# SCHEMA.net
KiCad netlist of a schematic drawn in Altium Designer
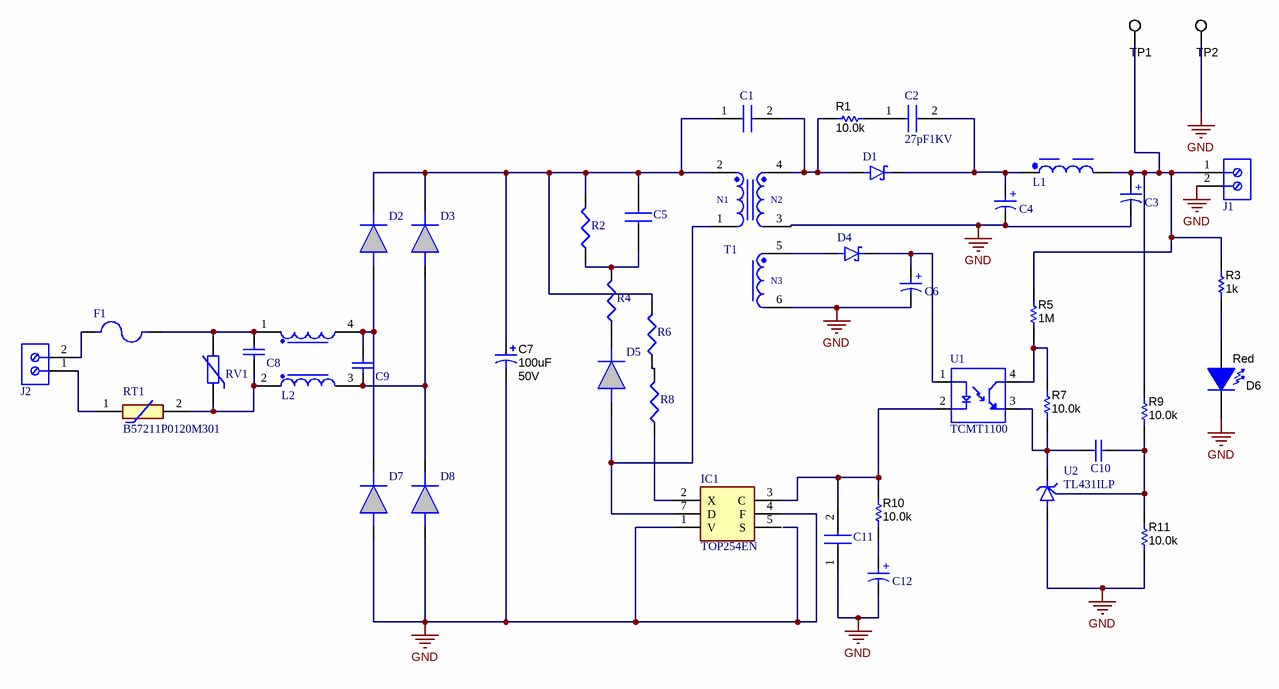
[diagram p0: SCHEMA.SchDoc]

(export (version "E")
  (design (tool "Eeschema 10.0.6"))
  (components
    (comp (ref "C1")
      (value "c270.22nf-250VAC")
      (footprint "440LT22R")
      (description "Capacitor")
      (fields
        (field (name "MANUFACTURER_PART_NUMBER") "440LT22-R")
        (field (name "MOUSER PART NUMBER") "75-440LT22-R")
      )
      (libsource (lib "INPUT_LIBRARY") (part "c270.22nf-250VAC"))
    )
    (comp (ref "C2")
      (value "27pF1KV")
      (footprint "S270K25SL0N63L6R")
      (description "Capacitor")
      (fields
        (field (name "MANUFACTURER_PART_NUMBER") "S270K25SL0N63L6R")
        (field (name "MOUSER PART NUMBER") "594-S270K25SL0N63L6R")
      )
      (libsource (lib "INPUT_LIBRARY") (part "27pF1KV"))
    )
    (comp (ref "C3")
      (value "180µF")
      (footprint "WCAP-PTG5_D8H8")
      (description "WCAP-PTG5 Aluminum Polymer Capacitor, Radial THT, D8 x H8mm, 180µF, 6.3V")
      (fields
        (field (name "MANUFACTURER PART NUMBER") "870025174001")
        (field (name "MANUFACTURER") "Wurth Elektronik")
      )
      (libsource (lib "INPUT_LIBRARY") (part "100uf 16v"))
    )
    (comp (ref "C4")
      (value "22uF")
      (footprint "WCAP-ATG8_D5H11")
      (description "WCAP-ATG8 Aluminum Electrolytic Capacitor, Radial, THT, D5 x H11mm, 22uF, 10V")
      (fields
        (field (name "MANUFACTURER PART NUMBER") "860010272001")
        (field (name "MANUFACTURER") "Wurth Elektronik")
      )
      (libsource (lib "INPUT_LIBRARY") (part "1800uf 25v"))
    )
    (comp (ref "C5")
      (value "FG26C0G2J391JNT06")
      (footprint "capacitor_ceramic")
      (description "MLCC with Dipped Radial Lead, Capacitance=390pF, LxWxT:5.5x6x3.5mm, Lead pitch:5mm")
      (fields (field (name "MOUSER PART NUMBER") "810-FG26C0G2J391JNT6"))
      (libsource (lib "INPUT_LIBRARY") (part "1.5 nF, 630 V, High Voltage Ceramic"))
    )
    (comp (ref "C6")
      (value "22uF")
      (footprint "WCAP-ATG8_D5H11")
      (description "WCAP-ATG8 Aluminum Electrolytic Capacitor, Radial, THT, D5 x H11mm, 22uF, 10V")
      (fields
        (field (name "MANUFACTURER PART NUMBER") "860010272001")
        (field (name "MANUFACTURER") "Wurth Elektronik")
      )
      (libsource (lib "INPUT_LIBRARY") (part "1800uf 25v"))
    )
    (comp (ref "C7")
      (value "UBT1H101MPD1TD")
      (footprint "BT_1000x1250")
      (description "CAP, AL, 100 uF, 50 V, +/- 20%, TH")
      (fields
        (field (name "MANUFACTURER") "Nichicon")
        (field (name "VALUEDISPLAYED") "100uF")
        (field (name "VDC_V") "50V")
        (field (name "PUBLISHER") "Texas Instruments")
      )
      (libsource (lib "INPUT_LIBRARY") (part "CMP-0009918-2"))
    )
    (comp (ref "C8")
      (value "15nF")
      (footprint "WCAP-FTX2_L11W6H10")
      (description "WCAP-FTX2 Film Capacitor, THT, L11 x W6 x H10mm, 15nF, 275V")
      (fields
        (field (name "MANUFACTURER PART NUMBER") "890324022007")
        (field (name "MANUFACTURER") "Wurth Elektronik")
      )
      (libsource (lib "INPUT_LIBRARY") (part "100nF275V iNPUT choke"))
    )
    (comp (ref "C9")
      (value "15nF")
      (footprint "WCAP-FTX2_L11W6H10")
      (description "WCAP-FTX2 Film Capacitor, THT, L11 x W6 x H10mm, 15nF, 275V")
      (fields
        (field (name "MANUFACTURER PART NUMBER") "890324022007")
        (field (name "MANUFACTURER") "Wurth Elektronik")
      )
      (libsource (lib "INPUT_LIBRARY") (part "100nF275V iNPUT choke"))
    )
    (comp (ref "C10")
      (value "15nF")
      (footprint "WCAP-FTX2_L11W6H10")
      (description "WCAP-FTX2 Film Capacitor, THT, L11 x W6 x H10mm, 15nF, 275V")
      (fields
        (field (name "MANUFACTURER PART NUMBER") "890324022007")
        (field (name "MANUFACTURER") "Wurth Elektronik")
      )
      (libsource (lib "INPUT_LIBRARY") (part "100nF275V iNPUT choke"))
    )
    (comp (ref "C11")
      (value "0.1 μF, 50 V, Ceramic, X7R")
      (footprint "C322")
      (description "Capacitor")
      (fields
        (field (name "MANUFACTURER_PART_NUMBER") "C322C104K5R5TA")
        (field (name "MOUSER PART NUMBER") "80-C322C104K5R")
      )
      (libsource (lib "INPUT_LIBRARY") (part "0.1 μF, 50 V, Ceramic, X7R"))
    )
    (comp (ref "C12")
      (value "180µF")
      (footprint "WCAP-PTG5_D8H8")
      (description "WCAP-PTG5 Aluminum Polymer Capacitor, Radial THT, D8 x H8mm, 180µF, 6.3V")
      (fields
        (field (name "MANUFACTURER PART NUMBER") "870025174001")
        (field (name "MANUFACTURER") "Wurth Elektronik")
      )
      (libsource (lib "INPUT_LIBRARY") (part "100uf 16v"))
    )
    (comp (ref "D1")
      (value "diode shotcky")
      (footprint "DIOM7959X265N")
      (description "Diode Schottky 40 V 3A Surface Mount SMC (DO-214AB)")
      (fields (field (name "MF") "ON Semiconductor") (field (name "MP") "SS34"))
      (libsource (lib "INPUT_LIBRARY") (part "diode shotcky"))
    )
    (comp (ref "D2")
      (value "1N4006-E3_54")
      (footprint "DIOAD1405W86L465D235")
      (description "Vishay 1N4006-E3/54 Diode, 800V 1A, 2-Pin DO-204AL")
      (fields
        (field (name "MOUSER PART NUMBER") "625-1N4006-E3/54")
        (field (name "MANUFACTURER_PART_NUMBER") "1N4006-E3/54")
      )
      (libsource (lib "INPUT_LIBRARY") (part "1N4006-E3_54_1"))
    )
    (comp (ref "D3")
      (value "1N4006-E3_54")
      (footprint "DIOAD1405W86L465D235")
      (description "Vishay 1N4006-E3/54 Diode, 800V 1A, 2-Pin DO-204AL")
      (fields
        (field (name "MOUSER PART NUMBER") "625-1N4006-E3/54")
        (field (name "MANUFACTURER_PART_NUMBER") "1N4006-E3/54")
      )
      (libsource (lib "INPUT_LIBRARY") (part "1N4006-E3_54_1"))
    )
    (comp (ref "D4")
      (value "diode shotcky")
      (footprint "DIOM7959X265N")
      (description "Diode Schottky 40 V 3A Surface Mount SMC (DO-214AB)")
      (fields (field (name "MF") "ON Semiconductor") (field (name "MP") "SS34"))
      (libsource (lib "INPUT_LIBRARY") (part "diode shotcky"))
    )
    (comp (ref "D5")
      (value "RMPG06K-E3_54")
      (footprint "DIOAD1271W66L305D242")
      (description "Rectifiers 800 Volt 1.0A 250ns 40 Amp IFSM")
      (fields
        (field (name "MOUSER PART NUMBER") "625-RMPG06K-E3")
        (field (name "MANUFACTURER_PART_NUMBER") "RMPG06K-E3/54")
      )
      (libsource (lib "INPUT_LIBRARY") (part "RMPG06K-E3_54"))
    )
    (comp (ref "D6")
      (value "Red")
      (footprint "LED_LTST-C190_Red")
      (description "LED, Red, SMD")
      (fields
        (field (name "PARTNUMBER") "LTST-C190CKT")
        (field (name "MANUFACTURER") "Lite-On")
        (field (name "PUBLISHER") "Texas Instruments")
      )
      (libsource (lib "INPUT_LIBRARY") (part "LTST-C190CKT"))
    )
    (comp (ref "D7")
      (value "1N4006-E3_54")
      (footprint "DIOAD1405W86L465D235")
      (description "Vishay 1N4006-E3/54 Diode, 800V 1A, 2-Pin DO-204AL")
      (fields
        (field (name "MOUSER PART NUMBER") "625-1N4006-E3/54")
        (field (name "MANUFACTURER_PART_NUMBER") "1N4006-E3/54")
      )
      (libsource (lib "INPUT_LIBRARY") (part "1N4006-E3_54_1"))
    )
    (comp (ref "D8")
      (value "1N4006-E3_54")
      (footprint "DIOAD1405W86L465D235")
      (description "Vishay 1N4006-E3/54 Diode, 800V 1A, 2-Pin DO-204AL")
      (fields
        (field (name "MOUSER PART NUMBER") "625-1N4006-E3/54")
        (field (name "MANUFACTURER_PART_NUMBER") "1N4006-E3/54")
      )
      (libsource (lib "INPUT_LIBRARY") (part "1N4006-E3_54_1"))
    )
    (comp (ref "F1")
      (value "fuse tht")
      (footprint "FUSE_0154004.DR")
      (description "2-Pin Radial Fuse ¦ Rectangular ¦ Slow Blow ¦ UL ¦ Bulk Pack ¦ 250mA")
      (fields (field (name "MP") "0697H9200-02"))
      (libsource (lib "INPUT_LIBRARY") (part "fuse tht"))
    )
    (comp (ref "IC1")
      (value "TOP254EN")
      (footprint "TOP265EG")
      (description "Integrated Circuit")
      (fields (field (name "MOUSER PART NUMBER") "869-TOP254EN"))
      (libsource (lib "INPUT_LIBRARY") (part "TOP254EN"))
    )
    (comp (ref "J1")
      (value "691101710002")
      (footprint "691103110002")
      (description "WR-TBL Series 101 Horizontal Entry Modular, THT, pitch 5mm, 2p")
      (fields (field (name "MANUFACTURER") "Wurth Elektronik"))
      (libsource (lib "INPUT_LIBRARY") (part "691101710002"))
    )
    (comp (ref "J2")
      (value "691101710002")
      (footprint "Model Name")
      (description "WR-TBL Series 101 Horizontal Entry Modular, THT, pitch 5mm, 2p")
      (fields (field (name "MANUFACTURER") "Wurth Elektronik"))
      (libsource (lib "INPUT_LIBRARY") (part "691101710002"))
    )
    (comp (ref "L1")
      (value "3900µH, 0.18A")
      (footprint "INDUCTOR_TH")
      (description "WE-TI Radial Leaded Wire Wound Inductor, size 8075, 3900µH, 0.18A, 12Ω")
      (fields
        (field (name "MANUFACTURER PART NUMBER") "744730392")
        (field (name "MANUFACTURER") "Wurth Elektronik")
      )
      (libsource (lib "INPUT_LIBRARY") (part "744730392"))
    )
    (comp (ref "L2")
      (value "39mH")
      (footprint "WE-CMB_Type L_L27.5W18.5H33")
      (description "WE-CMB Common Mode Power Line Choke, THT, Type XS, 39mH, 0.3A, 3000mOhm")
      (fields
        (field (name "MANUFACTURER PART NUMBER") "744821039")
        (field (name "MANUFACTURER") "Wurth Elektronik")
      )
      (libsource (lib "INPUT_LIBRARY") (part "744821039"))
    )
    (comp (ref "R1")
      (value "ERA-3ARW103V")
      (footprint "RES_0603")
      (description "RES, 10.0 k, 0.05%, 0.1 W, AEC-Q200 Grade 0, 0603")
      (fields (field (name "MANUFACTURER") "Panasonic") (field (name "VALUEDISPLAYED") "10.0k"))
      (libsource (lib "INPUT_LIBRARY") (part "REStht"))
    )
    (comp (ref "R2")
      (value "0.15Ω")
      (footprint "RESAD1590W60L630D240")
      (description "WRIS-KSKE Thick Film Resistor, SMT, size 0402, 0.125W, 0.15Ω, +/-1%")
      (fields
        (field (name "MANUFACTURER PART NUMBER") "560050310002")
        (field (name "MANUFACTURER") "Wurth Elektronik")
      )
      (libsource (lib "INPUT_LIBRARY") (part "RES-THT"))
    )
    (comp (ref "R3")
      (value "1k")
      (footprint "0402L")
      (description "RES, 510, 5%, 0.063 W, 0402")
      (fields
        (field (name "PARTNUMBER") "CRCW0402510RJNED")
        (field (name "MANUFACTURER") "Vishay-Dale")
        (field (name "PUBLISHER") "Texas Instruments")
      )
      (libsource (lib "INPUT_LIBRARY") (part "CRCW0402510RJNED"))
    )
    (comp (ref "R4")
      (value "0.15Ω")
      (footprint "RESAD1590W60L630D240")
      (description "WRIS-KSKE Thick Film Resistor, SMT, size 0402, 0.125W, 0.15Ω, +/-1%")
      (fields
        (field (name "MANUFACTURER PART NUMBER") "560050310002")
        (field (name "MANUFACTURER") "Wurth Elektronik")
      )
      (libsource (lib "INPUT_LIBRARY") (part "RES-THT"))
    )
    (comp (ref "R5")
      (value "ERA-3ARW103V")
      (footprint "0603L")
      (description "RES, 10.0 k, 0.05%, 0.1 W, AEC-Q200 Grade 0, 0603")
      (fields (field (name "MANUFACTURER") "Panasonic") (field (name "VALUEDISPLAYED") "1M"))
      (libsource (lib "INPUT_LIBRARY") (part "RES-10K-0603"))
    )
    (comp (ref "R6")
      (value "0.15Ω")
      (footprint "RESAD1590W60L630D240")
      (description "WRIS-KSKE Thick Film Resistor, SMT, size 0402, 0.125W, 0.15Ω, +/-1%")
      (fields
        (field (name "MANUFACTURER PART NUMBER") "560050310002")
        (field (name "MANUFACTURER") "Wurth Elektronik")
      )
      (libsource (lib "INPUT_LIBRARY") (part "RES-THT"))
    )
    (comp (ref "R7")
      (value "ERA-3ARW103V")
      (footprint "RES_0603")
      (description "RES, 10.0 k, 0.05%, 0.1 W, AEC-Q200 Grade 0, 0603")
      (fields (field (name "MANUFACTURER") "Panasonic") (field (name "VALUEDISPLAYED") "10.0k"))
      (libsource (lib "INPUT_LIBRARY") (part "REStht"))
    )
    (comp (ref "R8")
      (value "0.15Ω")
      (footprint "RESAD1590W60L630D240")
      (description "WRIS-KSKE Thick Film Resistor, SMT, size 0402, 0.125W, 0.15Ω, +/-1%")
      (fields
        (field (name "MANUFACTURER PART NUMBER") "560050310002")
        (field (name "MANUFACTURER") "Wurth Elektronik")
      )
      (libsource (lib "INPUT_LIBRARY") (part "RES-THT"))
    )
    (comp (ref "R9")
      (value "ERA-3ARW103V")
      (footprint "RES_0603")
      (description "RES, 10.0 k, 0.05%, 0.1 W, AEC-Q200 Grade 0, 0603")
      (fields (field (name "MANUFACTURER") "Panasonic") (field (name "VALUEDISPLAYED") "10.0k"))
      (libsource (lib "INPUT_LIBRARY") (part "REStht"))
    )
    (comp (ref "R10")
      (value "ERA-3ARW103V")
      (footprint "RES_0603")
      (description "RES, 10.0 k, 0.05%, 0.1 W, AEC-Q200 Grade 0, 0603")
      (fields (field (name "MANUFACTURER") "Panasonic") (field (name "VALUEDISPLAYED") "10.0k"))
      (libsource (lib "INPUT_LIBRARY") (part "REStht"))
    )
    (comp (ref "R11")
      (value "ERA-3ARW103V")
      (footprint "RES_0603")
      (description "RES, 10.0 k, 0.05%, 0.1 W, AEC-Q200 Grade 0, 0603")
      (fields (field (name "MANUFACTURER") "Panasonic") (field (name "VALUEDISPLAYED") "10.0k"))
      (libsource (lib "INPUT_LIBRARY") (part "REStht"))
    )
    (comp (ref "RT1")
      (value "B57211P0120M301")
      (footprint "B57211P0***M3*1")
      (description "Thermistor")
      (fields (field (name "MOUSER PART NUMBER") "871-B57211P0120M301"))
      (libsource (lib "INPUT_LIBRARY") (part "B57211P0120M301"))
    )
    (comp (ref "RV1")
      (value "130VAC, 170VDC")
      (footprint "VARISTOR")
      (description "WE-VD Disk Varistor, THT, 130VAC, 170VDC, 410pF")
      (fields
        (field (name "MANUFACTURER PART NUMBER") "820411311")
        (field (name "MANUFACTURER") "Wurth Elektronik")
      )
      (libsource (lib "INPUT_LIBRARY") (part "820411311"))
    )
    (comp (ref "T1")
      (value "85-265Vin, 5Vout")
      (footprint "TRANSFORMER_E22")
      (description "WE-UNIT Off-Line Transformer, THT, E13/7/4_Vertical, 85-265Vin, 5Vout, 3W")
      (fields
        (field (name "MANUFACTURER PART NUMBER") "749118105")
        (field (name "MANUFACTURER") "Wurth Elektronik")
      )
      (libsource (lib "INPUT_LIBRARY") (part "749118105"))
    )
    (comp (ref "TP1")
      (value "5016")
      (footprint "Testpoint_Keystone_Compact")
      (description "Test Point, Compact, SMT")
      (fields (field (name "MANUFACTURER") "Keystone") (field (name "PUBLISHER") "Texas Instruments"))
      (libsource (lib "INPUT_LIBRARY") (part "5016"))
    )
    (comp (ref "TP2")
      (value "5016")
      (footprint "Testpoint_Keystone_Compact")
      (description "Test Point, Compact, SMT")
      (fields (field (name "MANUFACTURER") "Keystone") (field (name "PUBLISHER") "Texas Instruments"))
      (libsource (lib "INPUT_LIBRARY") (part "5016"))
    )
    (comp (ref "U1")
      (value "TCMT1100")
      (footprint "SOIC127P700X230-4N")
      (description "Optoisolator Transistor Output 3750Vrms 1 Channel 4-SOP")
      (fields
        (field (name "DIGI-KEY_PART_NUMBER") "TCMT1100CT-ND")
        (field (name "MF") "Vishay Semiconductor")
      )
      (libsource (lib "INPUT_LIBRARY") (part "TCMT1100"))
    )
    (comp (ref "U2")
      (value "TL431ILP")
      (footprint "TL431CLP")
      (description "Ic, Tl431ilp, Tl431, Tl431a, Tl4 31b, Tl432, Tl432a, Tl432b<Nv")
      (libsource (lib "INPUT_LIBRARY") (part "TL431ILP"))
    )
  )
  (nets
    (net (code "1") (name "GND") (class "Default")
      (node (ref "C11") (pin "1") (pinfunction "1_1") (pintype "passive"))
      (node (ref "C12") (pin "2") (pinfunction "N_2") (pintype "passive"))
      (node (ref "C3") (pin "2") (pinfunction "N_2") (pintype "passive"))
      (node (ref "C4") (pin "2") (pinfunction "N_2") (pintype "passive"))
      (node (ref "C6") (pin "2") (pinfunction "N_2") (pintype "passive"))
      (node (ref "C7") (pin "2") (pinfunction "-_2") (pintype "passive"))
      (node (ref "D6") (pin "2") (pinfunction "K_2") (pintype "passive"))
      (node (ref "D7") (pin "2") (pinfunction "A_2") (pintype "passive"))
      (node (ref "D8") (pin "2") (pinfunction "A_2") (pintype "passive"))
      (node (ref "IC1") (pin "1") (pinfunction "V_1") (pintype "passive"))
      (node (ref "IC1") (pin "4") (pinfunction "F_4") (pintype "passive"))
      (node (ref "J1") (pin "2") (pinfunction "2_2") (pintype "power_in"))
      (node (ref "R11") (pin "1") (pinfunction "1_1") (pintype "passive"))
      (node (ref "T1") (pin "3") (pinfunction "6_3") (pintype "passive"))
      (node (ref "T1") (pin "6") (pinfunction "6_6") (pintype "passive"))
      (node (ref "TP2") (pin "1") (pintype "passive"))
      (node (ref "U2") (pin "2") (pinfunction "A_2") (pintype "passive"))
    )
    (net (code "2") (name "Net-(C1-Pad2)") (class "Default")
      (node (ref "C1") (pin "2") (pinfunction "2_2") (pintype "passive"))
      (node (ref "D1") (pin "A") (pinfunction "A_A") (pintype "passive"))
      (node (ref "R1") (pin "2") (pinfunction "2_2") (pintype "passive"))
      (node (ref "T1") (pin "4") (pinfunction "4_4") (pintype "passive"))
    )
    (net (code "3") (name "Net-(C2-Pad1)") (class "Default")
      (node (ref "C2") (pin "1") (pinfunction "1_1") (pintype "passive"))
      (node (ref "R1") (pin "1") (pinfunction "1_1") (pintype "passive"))
    )
    (net (code "4") (name "Net-(C3-P)") (class "Default")
      (node (ref "C3") (pin "1") (pinfunction "P_1") (pintype "passive"))
      (node (ref "J1") (pin "1") (pinfunction "1_1") (pintype "power_in"))
      (node (ref "L1") (pin "2") (pinfunction "2_2") (pintype "passive"))
      (node (ref "R3") (pin "2") (pinfunction "2_2") (pintype "passive"))
      (node (ref "R5") (pin "1") (pinfunction "1_1") (pintype "passive"))
      (node (ref "R9") (pin "2") (pinfunction "2_2") (pintype "passive"))
      (node (ref "TP1") (pin "1") (pintype "passive"))
    )
    (net (code "5") (name "Net-(C4-P)") (class "Default")
      (node (ref "C2") (pin "2") (pinfunction "2_2") (pintype "passive"))
      (node (ref "C4") (pin "1") (pinfunction "P_1") (pintype "passive"))
      (node (ref "D1") (pin "C") (pinfunction "K_C") (pintype "passive"))
      (node (ref "L1") (pin "1") (pinfunction "1_1") (pintype "passive"))
    )
    (net (code "6") (name "Net-(C5-Pad2)") (class "Default")
      (node (ref "C5") (pin "2") (pinfunction "2_2") (pintype "passive"))
      (node (ref "R2") (pin "1") (pinfunction "1_1") (pintype "passive"))
      (node (ref "R4") (pin "2") (pinfunction "2_2") (pintype "passive"))
    )
    (net (code "7") (name "Net-(C6-P)") (class "Default")
      (node (ref "C6") (pin "1") (pinfunction "P_1") (pintype "passive"))
      (node (ref "D4") (pin "C") (pinfunction "K_C") (pintype "passive"))
      (node (ref "U1") (pin "1") (pinfunction "A_1") (pintype "passive"))
    )
    (net (code "8") (name "Net-(C7-+)") (class "Default")
      (node (ref "C1") (pin "1") (pinfunction "1_1") (pintype "passive"))
      (node (ref "C5") (pin "1") (pinfunction "1_1") (pintype "passive"))
      (node (ref "C7") (pin "1") (pinfunction "+_1") (pintype "passive"))
      (node (ref "D2") (pin "1") (pinfunction "K_1") (pintype "passive"))
      (node (ref "D3") (pin "1") (pinfunction "K_1") (pintype "passive"))
      (node (ref "R2") (pin "2") (pinfunction "2_2") (pintype "passive"))
      (node (ref "R6") (pin "2") (pinfunction "2_2") (pintype "passive"))
      (node (ref "T1") (pin "2") (pinfunction "3_2") (pintype "passive"))
    )
    (net (code "9") (name "Net-(C8-Pad1)") (class "Default")
      (node (ref "C8") (pin "1") (pinfunction "1_1") (pintype "passive"))
      (node (ref "L2") (pin "2") (pinfunction "2_2") (pintype "passive"))
      (node (ref "RT1") (pin "2") (pinfunction "2_2") (pintype "passive"))
      (node (ref "RV1") (pin "1") (pinfunction "1_1") (pintype "passive"))
    )
    (net (code "10") (name "Net-(C8-Pad2)") (class "Default")
      (node (ref "C8") (pin "2") (pinfunction "2_2") (pintype "passive"))
      (node (ref "F1") (pin "2") (pinfunction "2_2") (pintype "passive"))
      (node (ref "L2") (pin "1") (pinfunction "1_1") (pintype "passive"))
      (node (ref "RV1") (pin "2") (pinfunction "2_2") (pintype "passive"))
    )
    (net (code "11") (name "Net-(C12-P)") (class "Default")
      (node (ref "C12") (pin "1") (pinfunction "P_1") (pintype "passive"))
      (node (ref "R10") (pin "2") (pinfunction "2_2") (pintype "passive"))
    )
    (net (code "12") (name "Net-(D2-A)") (class "Default")
      (node (ref "C9") (pin "2") (pinfunction "2_2") (pintype "passive"))
      (node (ref "D2") (pin "2") (pinfunction "A_2") (pintype "passive"))
      (node (ref "D7") (pin "1") (pinfunction "K_1") (pintype "passive"))
      (node (ref "L2") (pin "4") (pinfunction "4_4") (pintype "passive"))
    )
    (net (code "13") (name "Net-(D3-A)") (class "Default")
      (node (ref "C9") (pin "1") (pinfunction "1_1") (pintype "passive"))
      (node (ref "D3") (pin "2") (pinfunction "A_2") (pintype "passive"))
      (node (ref "D8") (pin "1") (pinfunction "K_1") (pintype "passive"))
      (node (ref "L2") (pin "3") (pinfunction "3_3") (pintype "passive"))
    )
    (net (code "14") (name "Net-(D4-PadA)") (class "Default")
      (node (ref "D4") (pin "A") (pinfunction "A_A") (pintype "passive"))
      (node (ref "T1") (pin "5") (pinfunction "4_5") (pintype "passive"))
    )
    (net (code "15") (name "Net-(D5-A)") (class "Default")
      (node (ref "D5") (pin "2") (pinfunction "A_2") (pintype "passive"))
      (node (ref "IC1") (pin "7") (pinfunction "D_7") (pintype "passive"))
      (node (ref "T1") (pin "1") (pinfunction "1_1") (pintype "passive"))
    )
    (net (code "16") (name "Net-(D5-K)") (class "Default")
      (node (ref "D5") (pin "1") (pinfunction "K_1") (pintype "passive"))
      (node (ref "R4") (pin "1") (pinfunction "1_1") (pintype "passive"))
    )
    (net (code "17") (name "Net-(D6-A)") (class "Default")
      (node (ref "D6") (pin "1") (pinfunction "A_1") (pintype "passive"))
      (node (ref "R3") (pin "1") (pinfunction "1_1") (pintype "passive"))
    )
    (net (code "18") (name "Net-(F1-Pad1)") (class "Default")
      (node (ref "F1") (pin "1") (pinfunction "1_1") (pintype "passive"))
      (node (ref "J2") (pin "2") (pinfunction "2_2") (pintype "power_in"))
    )
    (net (code "19") (name "Net-(IC1-C)") (class "Default")
      (node (ref "C11") (pin "2") (pinfunction "2_2") (pintype "passive"))
      (node (ref "IC1") (pin "3") (pinfunction "C_3") (pintype "passive"))
      (node (ref "R10") (pin "1") (pinfunction "1_1") (pintype "passive"))
      (node (ref "U1") (pin "2") (pinfunction "C_2") (pintype "passive"))
    )
    (net (code "20") (name "Net-(IC1-X)") (class "Default")
      (node (ref "IC1") (pin "2") (pinfunction "X_2") (pintype "passive"))
      (node (ref "R8") (pin "1") (pinfunction "1_1") (pintype "passive"))
    )
    (net (code "21") (name "Net-(J2-Pad1)") (class "Default")
      (node (ref "J2") (pin "1") (pinfunction "1_1") (pintype "power_in"))
      (node (ref "RT1") (pin "1") (pinfunction "1_1") (pintype "passive"))
    )
    (net (code "22") (name "Net-(R6-Pad1)") (class "Default")
      (node (ref "R6") (pin "1") (pinfunction "1_1") (pintype "passive"))
      (node (ref "R8") (pin "2") (pinfunction "2_2") (pintype "passive"))
    )
    (net (code "23") (name "Net-(U1-CT)") (class "Default")
      (node (ref "R5") (pin "2") (pinfunction "2_2") (pintype "passive"))
      (node (ref "R7") (pin "1") (pinfunction "1_1") (pintype "passive"))
      (node (ref "U1") (pin "4") (pinfunction "CT_4") (pintype "passive"))
    )
    (net (code "24") (name "Net-(U1-ET)") (class "Default")
      (node (ref "C10") (pin "1") (pinfunction "1_1") (pintype "passive"))
      (node (ref "R7") (pin "2") (pinfunction "2_2") (pintype "passive"))
      (node (ref "U1") (pin "3") (pinfunction "ET_3") (pintype "passive"))
      (node (ref "U2") (pin "3") (pinfunction "C_3") (pintype "passive"))
    )
    (net (code "25") (name "Net-(U2-REF)") (class "Default")
      (node (ref "C10") (pin "2") (pinfunction "2_2") (pintype "passive"))
      (node (ref "R11") (pin "2") (pinfunction "2_2") (pintype "passive"))
      (node (ref "R9") (pin "1") (pinfunction "1_1") (pintype "passive"))
      (node (ref "U2") (pin "1") (pinfunction "REF_1") (pintype "passive"))
    )
    (net (code "26") (name "unconnected-(IC1-S-Pad5)") (class "Default")
      (node (ref "IC1") (pin "5") (pinfunction "S_5") (pintype "passive"))
    )
  )
)
